# powerBoard_v3.net
KiCad netlist of a schematic drawn in EAGLE
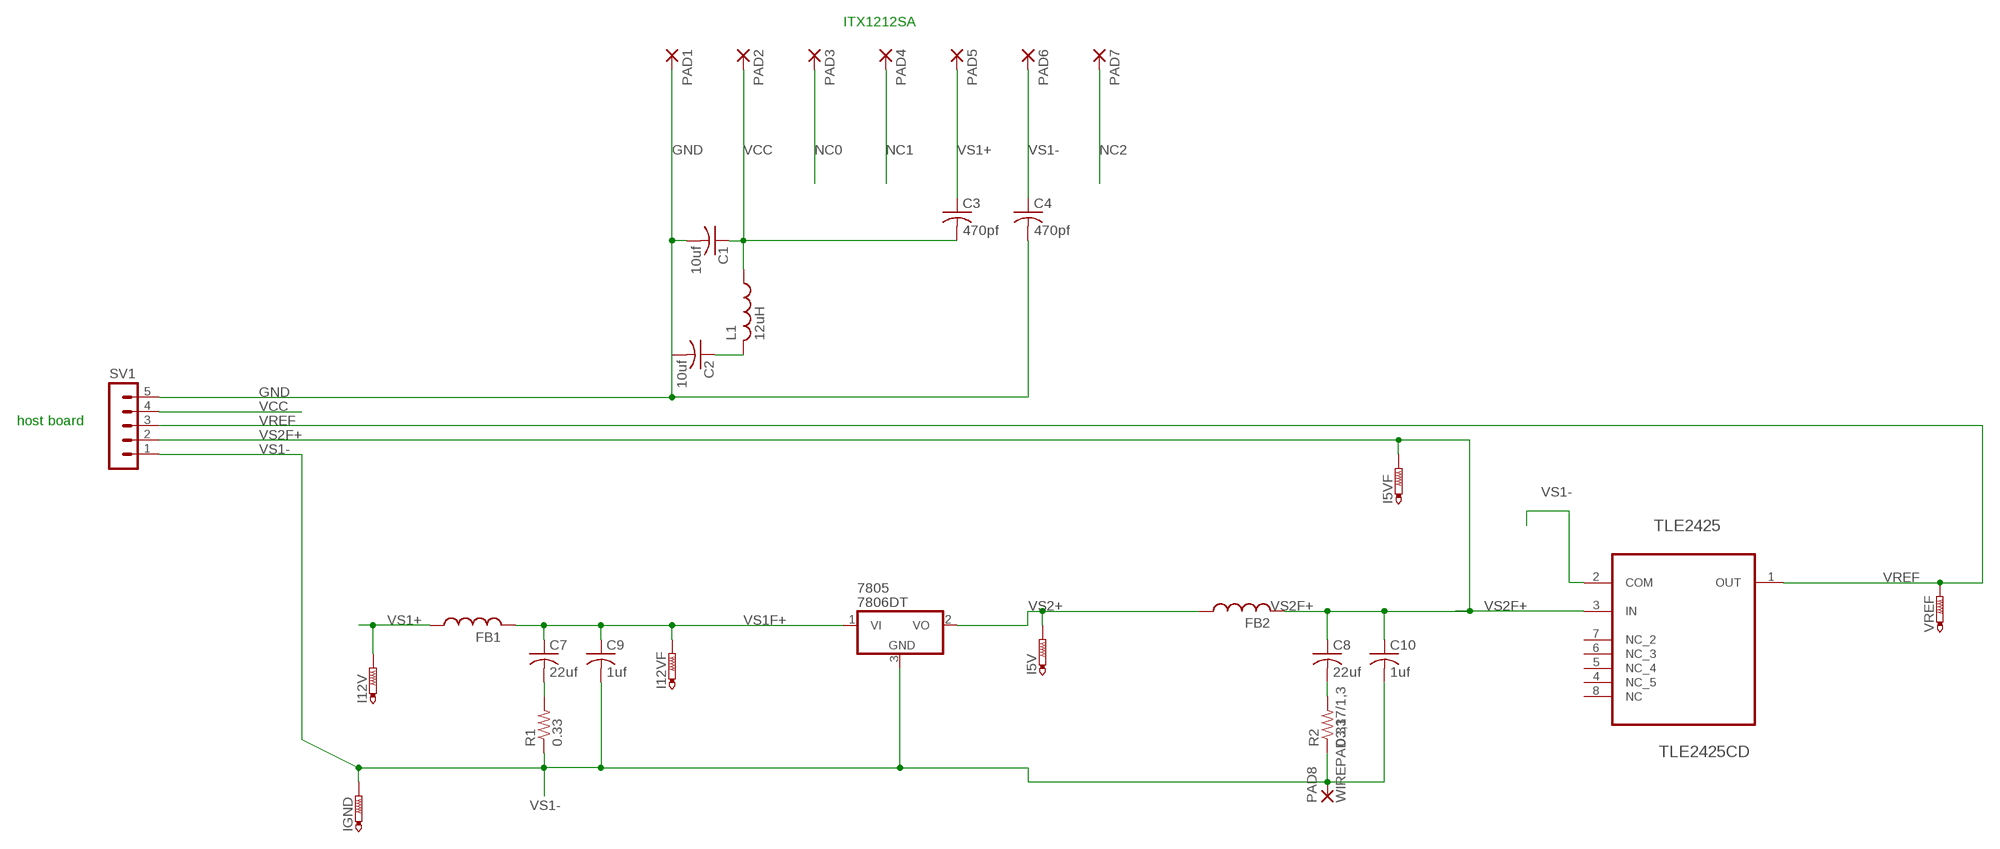
[diagram p0: schematic, sheet 1]

(export (version "E")
  (design (tool "Eeschema 10.0.6"))
  (components
    (comp (ref "7805")
      (value "7806DT")
      (footprint "eagle-import:TO252")
      (libsource (lib "eagle-import") (part "78DT06"))
    )
    (comp (ref "C1")
      (value "10uf")
      (footprint "eagle-import:C0805K")
      (libsource (lib "eagle-import") (part "C-USC0805K"))
    )
    (comp (ref "C2")
      (value "10uf")
      (footprint "eagle-import:C0805K")
      (libsource (lib "eagle-import") (part "C-USC0805K"))
    )
    (comp (ref "C3")
      (value "470pf")
      (footprint "eagle-import:C0805K")
      (libsource (lib "eagle-import") (part "C-USC0805K"))
    )
    (comp (ref "C4")
      (value "470pf")
      (footprint "eagle-import:C0805K")
      (libsource (lib "eagle-import") (part "C-USC0805K"))
    )
    (comp (ref "C7")
      (value "22uf")
      (footprint "eagle-import:C0805K")
      (libsource (lib "eagle-import") (part "C-USC0805K"))
    )
    (comp (ref "C8")
      (value "22uf")
      (footprint "eagle-import:C0805K")
      (libsource (lib "eagle-import") (part "C-USC0805K"))
    )
    (comp (ref "C9")
      (value "1uf")
      (footprint "eagle-import:C0805K")
      (libsource (lib "eagle-import") (part "C-USC0805K"))
    )
    (comp (ref "C10")
      (value "1uf")
      (footprint "eagle-import:C0805K")
      (libsource (lib "eagle-import") (part "C-USC0805K"))
    )
    (comp (ref "FB1")
      (value "L-USL2012C")
      (footprint "eagle-import:L2012C")
      (libsource (lib "eagle-import") (part "L-USL2012C"))
    )
    (comp (ref "FB2")
      (value "L-USL2012C")
      (footprint "eagle-import:L2012C")
      (libsource (lib "eagle-import") (part "L-USL2012C"))
    )
    (comp (ref "I5V")
      (value "PTR1PAD1-13")
      (footprint "eagle-import:P1-13")
      (libsource (lib "eagle-import") (part "PTR1PAD1-13"))
    )
    (comp (ref "I5VF")
      (value "PTR1PAD1-13")
      (footprint "eagle-import:P1-13")
      (libsource (lib "eagle-import") (part "PTR1PAD1-13"))
    )
    (comp (ref "I12V")
      (value "PTR1PAD1-13")
      (footprint "eagle-import:P1-13")
      (libsource (lib "eagle-import") (part "PTR1PAD1-13"))
    )
    (comp (ref "I12VF")
      (value "PTR1PAD1-13")
      (footprint "eagle-import:P1-13")
      (libsource (lib "eagle-import") (part "PTR1PAD1-13"))
    )
    (comp (ref "IGND")
      (value "PTR1PAD1-13")
      (footprint "eagle-import:P1-13")
      (libsource (lib "eagle-import") (part "PTR1PAD1-13"))
    )
    (comp (ref "L1")
      (value "12uH")
      (footprint "eagle-import:L2012C")
      (libsource (lib "eagle-import") (part "resistor_L-USL2012C"))
    )
    (comp (ref "PAD1")
      (value "SMD2")
      (footprint "eagle-import:SMD1,27-2,54")
      (libsource (lib "eagle-import") (part "SMD2"))
    )
    (comp (ref "PAD2")
      (value "SMD2")
      (footprint "eagle-import:SMD1,27-2,54")
      (libsource (lib "eagle-import") (part "SMD2"))
    )
    (comp (ref "PAD3")
      (value "SMD2")
      (footprint "eagle-import:SMD1,27-2,54")
      (libsource (lib "eagle-import") (part "SMD2"))
    )
    (comp (ref "PAD4")
      (value "SMD2")
      (footprint "eagle-import:SMD1,27-2,54")
      (libsource (lib "eagle-import") (part "SMD2"))
    )
    (comp (ref "PAD5")
      (value "SMD2")
      (footprint "eagle-import:SMD1,27-2,54")
      (libsource (lib "eagle-import") (part "SMD2"))
    )
    (comp (ref "PAD6")
      (value "SMD2")
      (footprint "eagle-import:SMD1,27-2,54")
      (libsource (lib "eagle-import") (part "SMD2"))
    )
    (comp (ref "PAD7")
      (value "SMD2")
      (footprint "eagle-import:SMD1,27-2,54")
      (libsource (lib "eagle-import") (part "SMD2"))
    )
    (comp (ref "PAD8")
      (value "WIREPAD3,17/1,3")
      (footprint "eagle-import:3,17_1,3")
      (libsource (lib "eagle-import") (part "WIREPAD3,17/1,3"))
    )
    (comp (ref "R1")
      (value "0.33")
      (footprint "eagle-import:R2012W")
      (libsource (lib "eagle-import") (part "R-US_R2012W"))
    )
    (comp (ref "R2")
      (value "0.33")
      (footprint "eagle-import:R2012W")
      (libsource (lib "eagle-import") (part "R-US_R2012W"))
    )
    (comp (ref "SV1")
      (value "MA05-1")
      (footprint "eagle-import:MA05-1")
      (libsource (lib "eagle-import") (part "MA05-1"))
    )
    (comp (ref "TLE2425")
      (value "TLE2425CD")
      (footprint "eagle-import:SOIC127P600X175-8N")
      (libsource (lib "eagle-import") (part "TLE2425CD"))
    )
    (comp (ref "VREF")
      (value "PTR1PAD1-13")
      (footprint "eagle-import:P1-13")
      (libsource (lib "eagle-import") (part "PTR1PAD1-13"))
    )
  )
  (nets
    (net (code "1") (name "/GND") (class "Default")
      (node (ref "C1") (pin "2") (pinfunction "2_2") (pintype "passive"))
      (node (ref "C2") (pin "2") (pinfunction "2_2") (pintype "passive"))
      (node (ref "C4") (pin "2") (pinfunction "2_2") (pintype "passive"))
      (node (ref "PAD1") (pin "1") (pinfunction "P_1") (pintype "passive"))
      (node (ref "SV1") (pin "5") (pinfunction "5_5") (pintype "passive"))
    )
    (net (code "2") (name "/NC0") (class "Default")
      (node (ref "PAD3") (pin "1") (pinfunction "P_1") (pintype "passive"))
    )
    (net (code "3") (name "/NC1") (class "Default")
      (node (ref "PAD4") (pin "1") (pinfunction "P_1") (pintype "passive"))
    )
    (net (code "4") (name "/NC2") (class "Default")
      (node (ref "PAD7") (pin "1") (pinfunction "P_1") (pintype "passive"))
    )
    (net (code "5") (name "/VCC") (class "Default")
      (node (ref "C1") (pin "1") (pinfunction "1_1") (pintype "passive"))
      (node (ref "C3") (pin "2") (pinfunction "2_2") (pintype "passive"))
      (node (ref "L1") (pin "1") (pinfunction "1_1") (pintype "passive"))
      (node (ref "PAD2") (pin "1") (pinfunction "P_1") (pintype "passive"))
      (node (ref "SV1") (pin "4") (pinfunction "4_4") (pintype "passive"))
    )
    (net (code "6") (name "/VREF") (class "Default")
      (node (ref "SV1") (pin "3") (pinfunction "3_3") (pintype "passive"))
      (node (ref "TLE2425") (pin "1") (pinfunction "OUT_1") (pintype "output"))
      (node (ref "VREF") (pin "TP") (pinfunction "TP_TP") (pintype "input"))
    )
    (net (code "7") (name "/VS1+") (class "Default")
      (node (ref "C3") (pin "1") (pinfunction "1_1") (pintype "passive"))
      (node (ref "FB1") (pin "1") (pinfunction "1_1") (pintype "passive"))
      (node (ref "I12V") (pin "TP") (pinfunction "TP_TP") (pintype "input"))
      (node (ref "PAD5") (pin "1") (pinfunction "P_1") (pintype "passive"))
    )
    (net (code "8") (name "/VS1-") (class "Default")
      (node (ref "7805") (pin "3") (pinfunction "GND_3") (pintype "passive"))
      (node (ref "C10") (pin "2") (pinfunction "2_2") (pintype "passive"))
      (node (ref "C4") (pin "1") (pinfunction "1_1") (pintype "passive"))
      (node (ref "C9") (pin "2") (pinfunction "2_2") (pintype "passive"))
      (node (ref "IGND") (pin "TP") (pinfunction "TP_TP") (pintype "input"))
      (node (ref "PAD6") (pin "1") (pinfunction "P_1") (pintype "passive"))
      (node (ref "PAD8") (pin "1") (pinfunction "P_1") (pintype "passive"))
      (node (ref "R1") (pin "1") (pinfunction "1_1") (pintype "passive"))
      (node (ref "R2") (pin "1") (pinfunction "1_1") (pintype "passive"))
      (node (ref "SV1") (pin "1") (pinfunction "1_1") (pintype "passive"))
      (node (ref "TLE2425") (pin "2") (pinfunction "COM_2") (pintype "passive"))
    )
    (net (code "9") (name "/VS1F+") (class "Default")
      (node (ref "7805") (pin "1") (pinfunction "VI_1") (pintype "input"))
      (node (ref "C7") (pin "1") (pinfunction "1_1") (pintype "passive"))
      (node (ref "C9") (pin "1") (pinfunction "1_1") (pintype "passive"))
      (node (ref "FB1") (pin "2") (pinfunction "2_2") (pintype "passive"))
      (node (ref "I12VF") (pin "TP") (pinfunction "TP_TP") (pintype "input"))
    )
    (net (code "10") (name "/VS2+") (class "Default")
      (node (ref "7805") (pin "2") (pinfunction "VO_2") (pintype "passive"))
      (node (ref "FB2") (pin "1") (pinfunction "1_1") (pintype "passive"))
      (node (ref "I5V") (pin "TP") (pinfunction "TP_TP") (pintype "input"))
    )
    (net (code "11") (name "/VS2F+") (class "Default")
      (node (ref "C10") (pin "1") (pinfunction "1_1") (pintype "passive"))
      (node (ref "C8") (pin "1") (pinfunction "1_1") (pintype "passive"))
      (node (ref "FB2") (pin "2") (pinfunction "2_2") (pintype "passive"))
      (node (ref "I5VF") (pin "TP") (pinfunction "TP_TP") (pintype "input"))
      (node (ref "SV1") (pin "2") (pinfunction "2_2") (pintype "passive"))
      (node (ref "TLE2425") (pin "3") (pinfunction "IN_3") (pintype "input"))
    )
    (net (code "12") (name "Net-(C2-Pad1)") (class "Default")
      (node (ref "C2") (pin "1") (pinfunction "1_1") (pintype "passive"))
      (node (ref "L1") (pin "2") (pinfunction "2_2") (pintype "passive"))
    )
    (net (code "13") (name "Net-(C7-Pad2)") (class "Default")
      (node (ref "C7") (pin "2") (pinfunction "2_2") (pintype "passive"))
      (node (ref "R1") (pin "2") (pinfunction "2_2") (pintype "passive"))
    )
    (net (code "14") (name "Net-(C8-Pad2)") (class "Default")
      (node (ref "C8") (pin "2") (pinfunction "2_2") (pintype "passive"))
      (node (ref "R2") (pin "2") (pinfunction "2_2") (pintype "passive"))
    )
    (net (code "15") (name "unconnected-(TLE2425-NC-Pad8)") (class "Default")
      (node (ref "TLE2425") (pin "8") (pinfunction "NC_8") (pintype "no_connect"))
    )
    (net (code "16") (name "unconnected-(TLE2425-NC_2-Pad7)") (class "Default")
      (node (ref "TLE2425") (pin "7") (pinfunction "NC_2_7") (pintype "no_connect"))
    )
    (net (code "17") (name "unconnected-(TLE2425-NC_3-Pad6)") (class "Default")
      (node (ref "TLE2425") (pin "6") (pinfunction "NC_3_6") (pintype "no_connect"))
    )
    (net (code "18") (name "unconnected-(TLE2425-NC_4-Pad5)") (class "Default")
      (node (ref "TLE2425") (pin "5") (pinfunction "NC_4_5") (pintype "no_connect"))
    )
    (net (code "19") (name "unconnected-(TLE2425-NC_5-Pad4)") (class "Default")
      (node (ref "TLE2425") (pin "4") (pinfunction "NC_5_4") (pintype "no_connect"))
    )
  )
)
